# tp4056.net
KiCad netlist of a schematic drawn in Altium Designer
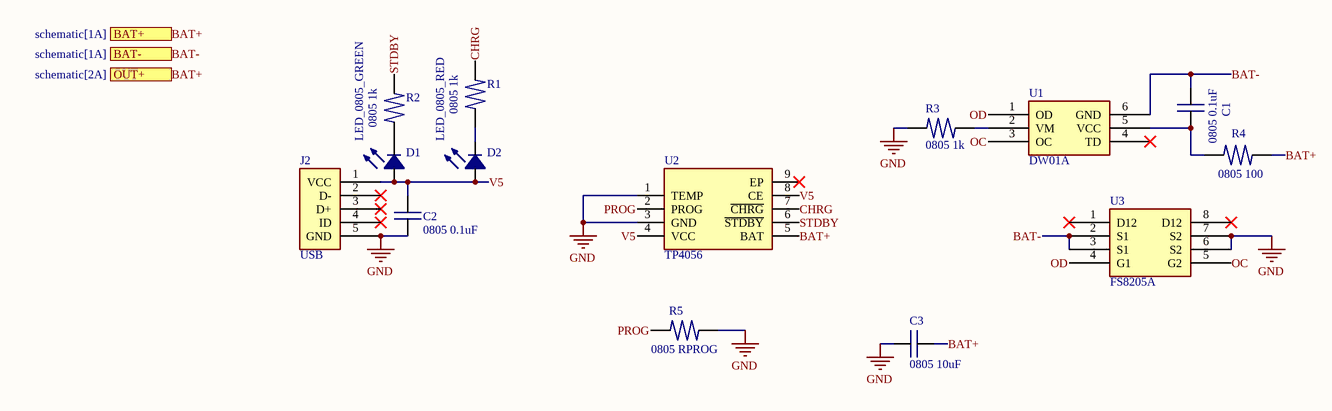
[diagram p0: tp4056.SchDoc]

(export (version "E")
  (design (tool "Eeschema 10.0.6"))
  (components
    (comp (ref "C1")
      (value "0805 0.1uF")
      (footprint "CAPACITOR 0805")
      (libsource (lib "Ceramic Capacitor") (part "CAPACITOR 0805"))
    )
    (comp (ref "C2")
      (value "0805 0.1uF")
      (footprint "CAPACITOR 0805")
      (libsource (lib "Ceramic Capacitor") (part "CAPACITOR 0805"))
    )
    (comp (ref "C3")
      (value "0805 10uF")
      (footprint "CAPACITOR 0805")
      (libsource (lib "Ceramic Capacitor") (part "CAPACITOR 0805"))
    )
    (comp (ref "D1")
      (value "LED_0805_GREEN")
      (footprint "LED_0805_GREEN")
      (libsource (lib "LED") (part "LED_0805_GREEN"))
    )
    (comp (ref "D2")
      (value "LED_0805_RED")
      (footprint "LED_0805_RED")
      (libsource (lib "LED") (part "LED_0805_RED"))
    )
    (comp (ref "J2") (value "USB") (footprint "USB") (libsource (lib "Connectors") (part "USB")))
    (comp (ref "R1")
      (value "0805 1k")
      (footprint "RESISTOR_0805")
      (libsource (lib "Resistors") (part "RESISTOR_0805"))
    )
    (comp (ref "R2")
      (value "0805 1k")
      (footprint "RESISTOR_0805")
      (libsource (lib "Resistors") (part "RESISTOR_0805"))
    )
    (comp (ref "R3")
      (value "0805 1k")
      (footprint "RESISTOR_0805")
      (libsource (lib "Resistors") (part "RESISTOR_0805"))
    )
    (comp (ref "R4")
      (value "0805 100")
      (footprint "RESISTOR_0805")
      (libsource (lib "Resistors") (part "RESISTOR_0805"))
    )
    (comp (ref "R5")
      (value "0805 RPROG")
      (footprint "RESISTOR_0805")
      (libsource (lib "Resistors") (part "RESISTOR_0805"))
    )
    (comp (ref "U1")
      (value "DW01A")
      (footprint "DW01A")
      (description "BATTERY PROTECTION IC")
      (libsource (lib "Random") (part "DW01A"))
    )
    (comp (ref "U2")
      (value "TP4056")
      (footprint "TP4056")
      (description "CHIP BATTERY CHARGER")
      (libsource (lib "Random") (part "TP4056"))
    )
    (comp (ref "U3")
      (value "FS8205A")
      (footprint "FS8205A")
      (description "20V DUAL N-CHANNEL MOSFET TSSOP-8")
      (libsource (lib "Transistors") (part "FS8205A"))
    )
  )
  (nets
    (net (code "1") (name "/BAT+") (class "Default")
      (node (ref "C3") (pin "2") (pinfunction "2_2") (pintype "passive"))
      (node (ref "R4") (pin "2") (pinfunction "2_2") (pintype "passive"))
      (node (ref "U2") (pin "5") (pinfunction "BAT_5") (pintype "passive"))
    )
    (net (code "2") (name "/BAT-") (class "Default")
      (node (ref "C1") (pin "2") (pinfunction "2_2") (pintype "passive"))
      (node (ref "U1") (pin "6") (pinfunction "GND_6") (pintype "passive"))
      (node (ref "U3") (pin "2") (pinfunction "S1_2") (pintype "passive"))
      (node (ref "U3") (pin "3") (pinfunction "S1_3") (pintype "passive"))
    )
    (net (code "3") (name "/CHRG") (class "Default")
      (node (ref "R1") (pin "2") (pinfunction "2_2") (pintype "passive"))
      (node (ref "U2") (pin "7") (pinfunction "~{CHRG}_7") (pintype "passive"))
    )
    (net (code "4") (name "/OC") (class "Default")
      (node (ref "U1") (pin "3") (pinfunction "OC_3") (pintype "passive"))
      (node (ref "U3") (pin "5") (pinfunction "G2_5") (pintype "passive"))
    )
    (net (code "5") (name "/OD") (class "Default")
      (node (ref "U1") (pin "1") (pinfunction "OD_1") (pintype "passive"))
      (node (ref "U3") (pin "4") (pinfunction "G1_4") (pintype "passive"))
    )
    (net (code "6") (name "/PROG") (class "Default")
      (node (ref "R5") (pin "1") (pinfunction "1_1") (pintype "passive"))
      (node (ref "U2") (pin "2") (pinfunction "PROG_2") (pintype "passive"))
    )
    (net (code "7") (name "/STDBY") (class "Default")
      (node (ref "R2") (pin "2") (pinfunction "2_2") (pintype "passive"))
      (node (ref "U2") (pin "6") (pinfunction "~{STDBY}_6") (pintype "passive"))
    )
    (net (code "8") (name "/V5") (class "Default")
      (node (ref "C2") (pin "2") (pinfunction "2_2") (pintype "passive"))
      (node (ref "D1") (pin "1") (pinfunction "1_1") (pintype "passive"))
      (node (ref "D2") (pin "1") (pinfunction "1_1") (pintype "passive"))
      (node (ref "J2") (pin "1") (pinfunction "VCC_1") (pintype "passive"))
      (node (ref "U2") (pin "4") (pinfunction "VCC_4") (pintype "passive"))
      (node (ref "U2") (pin "8") (pinfunction "CE_8") (pintype "passive"))
    )
    (net (code "9") (name "GND") (class "Default")
      (node (ref "C2") (pin "1") (pinfunction "1_1") (pintype "passive"))
      (node (ref "C3") (pin "1") (pinfunction "1_1") (pintype "passive"))
      (node (ref "J2") (pin "5") (pinfunction "GND_5") (pintype "passive"))
      (node (ref "R3") (pin "2") (pinfunction "2_2") (pintype "passive"))
      (node (ref "R5") (pin "2") (pinfunction "2_2") (pintype "passive"))
      (node (ref "U2") (pin "1") (pinfunction "TEMP_1") (pintype "passive"))
      (node (ref "U2") (pin "3") (pinfunction "GND_3") (pintype "passive"))
      (node (ref "U3") (pin "6") (pinfunction "S2_6") (pintype "passive"))
      (node (ref "U3") (pin "7") (pinfunction "S2_7") (pintype "passive"))
    )
    (net (code "10") (name "Net-(D1-Pad2)") (class "Default")
      (node (ref "D1") (pin "2") (pinfunction "2_2") (pintype "passive"))
      (node (ref "R2") (pin "1") (pinfunction "1_1") (pintype "passive"))
    )
    (net (code "11") (name "Net-(D2-Pad2)") (class "Default")
      (node (ref "D2") (pin "2") (pinfunction "2_2") (pintype "passive"))
      (node (ref "R1") (pin "1") (pinfunction "1_1") (pintype "passive"))
    )
    (net (code "12") (name "Net-(U1-VCC)") (class "Default")
      (node (ref "C1") (pin "1") (pinfunction "1_1") (pintype "passive"))
      (node (ref "R4") (pin "1") (pinfunction "1_1") (pintype "passive"))
      (node (ref "U1") (pin "5") (pinfunction "VCC_5") (pintype "passive"))
    )
    (net (code "13") (name "Net-(U1-VM)") (class "Default")
      (node (ref "R3") (pin "1") (pinfunction "1_1") (pintype "passive"))
      (node (ref "U1") (pin "2") (pinfunction "VM_2") (pintype "passive"))
    )
    (net (code "14") (name "unconnected-(J2-D+-Pad3)") (class "Default")
      (node (ref "J2") (pin "3") (pinfunction "D+_3") (pintype "passive+no_connect"))
    )
    (net (code "15") (name "unconnected-(J2-D--Pad2)") (class "Default")
      (node (ref "J2") (pin "2") (pinfunction "D-_2") (pintype "passive+no_connect"))
    )
    (net (code "16") (name "unconnected-(J2-ID-Pad4)") (class "Default")
      (node (ref "J2") (pin "4") (pinfunction "ID_4") (pintype "passive+no_connect"))
    )
    (net (code "17") (name "unconnected-(U1-TD-Pad4)") (class "Default")
      (node (ref "U1") (pin "4") (pinfunction "TD_4") (pintype "passive+no_connect"))
    )
    (net (code "18") (name "unconnected-(U2-EP-Pad9)") (class "Default")
      (node (ref "U2") (pin "9") (pinfunction "EP_9") (pintype "passive+no_connect"))
    )
    (net (code "19") (name "unconnected-(U3-D12-Pad1)") (class "Default")
      (node (ref "U3") (pin "1") (pinfunction "D12_1") (pintype "passive+no_connect"))
    )
    (net (code "20") (name "unconnected-(U3-D12-Pad8)") (class "Default")
      (node (ref "U3") (pin "8") (pinfunction "D12_8") (pintype "passive+no_connect"))
    )
  )
)
